# Charge_Amp.net
KiCad netlist of a schematic drawn in Altium Designer
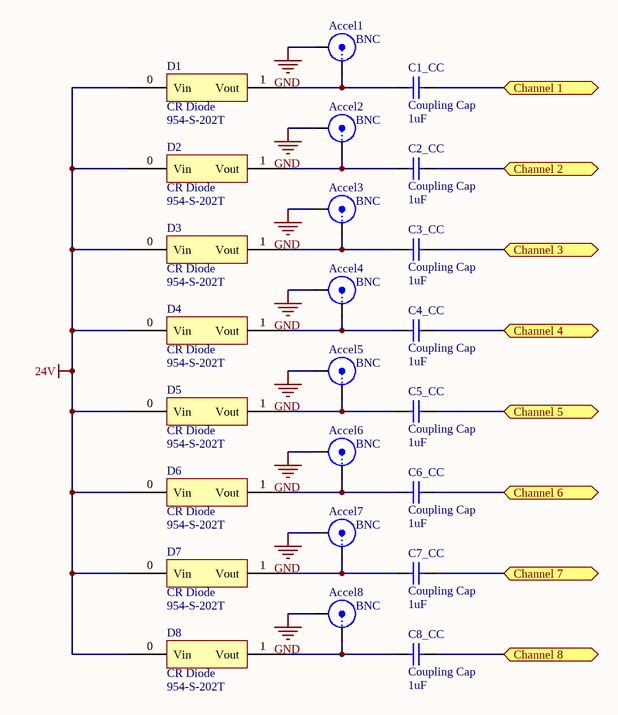
[diagram p0: Charge Amp.SchDoc]

(export (version "E")
  (design (tool "Eeschema 10.0.6"))
  (components
    (comp (ref "Accel1")
      (value "BNC")
      (footprint "BNC_RA CON")
      (description "BNC Elbow Connector")
      (fields (field (name "PUBLISHER") "Altium Limited"))
      (libsource (lib "Miscellaneous Connectors") (part "BNC"))
    )
    (comp (ref "Accel2")
      (value "BNC")
      (footprint "BNC_RA CON")
      (description "BNC Elbow Connector")
      (fields (field (name "PUBLISHER") "Altium Limited"))
      (libsource (lib "Miscellaneous Connectors") (part "BNC"))
    )
    (comp (ref "Accel3")
      (value "BNC")
      (footprint "BNC_RA CON")
      (description "BNC Elbow Connector")
      (fields (field (name "PUBLISHER") "Altium Limited"))
      (libsource (lib "Miscellaneous Connectors") (part "BNC"))
    )
    (comp (ref "Accel4")
      (value "BNC")
      (footprint "BNC_RA CON")
      (description "BNC Elbow Connector")
      (fields (field (name "PUBLISHER") "Altium Limited"))
      (libsource (lib "Miscellaneous Connectors") (part "BNC"))
    )
    (comp (ref "Accel5")
      (value "BNC")
      (footprint "BNC_RA CON")
      (description "BNC Elbow Connector")
      (fields (field (name "PUBLISHER") "Altium Limited"))
      (libsource (lib "Miscellaneous Connectors") (part "BNC"))
    )
    (comp (ref "Accel6")
      (value "BNC")
      (footprint "BNC_RA CON")
      (description "BNC Elbow Connector")
      (fields (field (name "PUBLISHER") "Altium Limited"))
      (libsource (lib "Miscellaneous Connectors") (part "BNC"))
    )
    (comp (ref "Accel7")
      (value "BNC")
      (footprint "BNC_RA CON")
      (description "BNC Elbow Connector")
      (fields (field (name "PUBLISHER") "Altium Limited"))
      (libsource (lib "Miscellaneous Connectors") (part "BNC"))
    )
    (comp (ref "Accel8")
      (value "BNC")
      (footprint "BNC_RA CON")
      (description "BNC Elbow Connector")
      (fields (field (name "PUBLISHER") "Altium Limited"))
      (libsource (lib "Miscellaneous Connectors") (part "BNC"))
    )
    (comp (ref "C1_CC")
      (value "Coupling Cap")
      (footprint "C1206")
      (description "Capacitor (Semiconductor SIM Model)")
      (fields (field (name "ALTIUM_VALUE") "1uF") (field (name "PUBLISHER") "Altium Limited"))
      (libsource (lib "Miscellaneous Devices") (part "Cap Semi"))
    )
    (comp (ref "C2_CC")
      (value "Coupling Cap")
      (footprint "C1206")
      (description "Capacitor (Semiconductor SIM Model)")
      (fields (field (name "ALTIUM_VALUE") "1uF") (field (name "PUBLISHER") "Altium Limited"))
      (libsource (lib "Miscellaneous Devices") (part "Cap Semi"))
    )
    (comp (ref "C3_CC")
      (value "Coupling Cap")
      (footprint "C1206")
      (description "Capacitor (Semiconductor SIM Model)")
      (fields (field (name "ALTIUM_VALUE") "1uF") (field (name "PUBLISHER") "Altium Limited"))
      (libsource (lib "Miscellaneous Devices") (part "Cap Semi"))
    )
    (comp (ref "C4_CC")
      (value "Coupling Cap")
      (footprint "C1206")
      (description "Capacitor (Semiconductor SIM Model)")
      (fields (field (name "ALTIUM_VALUE") "1uF") (field (name "PUBLISHER") "Altium Limited"))
      (libsource (lib "Miscellaneous Devices") (part "Cap Semi"))
    )
    (comp (ref "C5_CC")
      (value "Coupling Cap")
      (footprint "C1206")
      (description "Capacitor (Semiconductor SIM Model)")
      (fields (field (name "ALTIUM_VALUE") "1uF") (field (name "PUBLISHER") "Altium Limited"))
      (libsource (lib "Miscellaneous Devices") (part "Cap Semi"))
    )
    (comp (ref "C6_CC")
      (value "Coupling Cap")
      (footprint "C1206")
      (description "Capacitor (Semiconductor SIM Model)")
      (fields (field (name "ALTIUM_VALUE") "1uF") (field (name "PUBLISHER") "Altium Limited"))
      (libsource (lib "Miscellaneous Devices") (part "Cap Semi"))
    )
    (comp (ref "C7_CC")
      (value "Coupling Cap")
      (footprint "C1206")
      (description "Capacitor (Semiconductor SIM Model)")
      (fields (field (name "ALTIUM_VALUE") "1uF") (field (name "PUBLISHER") "Altium Limited"))
      (libsource (lib "Miscellaneous Devices") (part "Cap Semi"))
    )
    (comp (ref "C8_CC")
      (value "Coupling Cap")
      (footprint "C1206")
      (description "Capacitor (Semiconductor SIM Model)")
      (fields (field (name "ALTIUM_VALUE") "1uF") (field (name "PUBLISHER") "Altium Limited"))
      (libsource (lib "Miscellaneous Devices") (part "Cap Semi"))
    )
    (comp (ref "D1")
      (value "CR Diode")
      (footprint "CR Diode - duplicate1")
      (description "Current Regulator Diodes 100V 2mA")
      (fields (field (name "SUPPLIER PART NUMBER 1") "954-S-202T"))
      (libsource (lib "S-202T") (part "Diode_1"))
    )
    (comp (ref "D2")
      (value "CR Diode")
      (footprint "CR Diode - duplicate1")
      (description "Current Regulator Diodes 100V 2mA")
      (fields (field (name "SUPPLIER PART NUMBER 1") "954-S-202T"))
      (libsource (lib "S-202T") (part "Diode_1"))
    )
    (comp (ref "D3")
      (value "CR Diode")
      (footprint "CR Diode - duplicate1")
      (description "Current Regulator Diodes 100V 2mA")
      (fields (field (name "SUPPLIER PART NUMBER 1") "954-S-202T"))
      (libsource (lib "S-202T") (part "Diode_1"))
    )
    (comp (ref "D4")
      (value "CR Diode")
      (footprint "CR Diode - duplicate1")
      (description "Current Regulator Diodes 100V 2mA")
      (fields (field (name "SUPPLIER PART NUMBER 1") "954-S-202T"))
      (libsource (lib "S-202T") (part "Diode_1"))
    )
    (comp (ref "D5")
      (value "CR Diode")
      (footprint "CR Diode - duplicate1")
      (description "Current Regulator Diodes 100V 2mA")
      (fields (field (name "SUPPLIER PART NUMBER 1") "954-S-202T"))
      (libsource (lib "S-202T") (part "Diode_1"))
    )
    (comp (ref "D6")
      (value "CR Diode")
      (footprint "CR Diode - duplicate1")
      (description "Current Regulator Diodes 100V 2mA")
      (fields (field (name "SUPPLIER PART NUMBER 1") "954-S-202T"))
      (libsource (lib "S-202T") (part "Diode_1"))
    )
    (comp (ref "D7")
      (value "CR Diode")
      (footprint "CR Diode - duplicate1")
      (description "Current Regulator Diodes 100V 2mA")
      (fields (field (name "SUPPLIER PART NUMBER 1") "954-S-202T"))
      (libsource (lib "S-202T") (part "Diode_1"))
    )
    (comp (ref "D8")
      (value "CR Diode")
      (footprint "CR Diode - duplicate1")
      (description "Current Regulator Diodes 100V 2mA")
      (fields (field (name "SUPPLIER PART NUMBER 1") "954-S-202T"))
      (libsource (lib "S-202T") (part "Diode_1"))
    )
  )
  (nets
    (net (code "1") (name "/Channel 1") (class "Default")
      (node (ref "C1_CC") (pin "2") (pinfunction "2_2") (pintype "passive"))
    )
    (net (code "2") (name "/Channel 2") (class "Default")
      (node (ref "C2_CC") (pin "2") (pinfunction "2_2") (pintype "passive"))
    )
    (net (code "3") (name "/Channel 3") (class "Default")
      (node (ref "C3_CC") (pin "2") (pinfunction "2_2") (pintype "passive"))
    )
    (net (code "4") (name "/Channel 4") (class "Default")
      (node (ref "C4_CC") (pin "2") (pinfunction "2_2") (pintype "passive"))
    )
    (net (code "5") (name "/Channel 5") (class "Default")
      (node (ref "C5_CC") (pin "2") (pinfunction "2_2") (pintype "passive"))
    )
    (net (code "6") (name "/Channel 6") (class "Default")
      (node (ref "C6_CC") (pin "2") (pinfunction "2_2") (pintype "passive"))
    )
    (net (code "7") (name "/Channel 7") (class "Default")
      (node (ref "C7_CC") (pin "2") (pinfunction "2_2") (pintype "passive"))
    )
    (net (code "8") (name "/Channel 8") (class "Default")
      (node (ref "C8_CC") (pin "2") (pinfunction "2_2") (pintype "passive"))
    )
    (net (code "9") (name "24V") (class "Default")
      (node (ref "D1") (pin "0") (pinfunction "Vin_0") (pintype "passive"))
      (node (ref "D2") (pin "0") (pinfunction "Vin_0") (pintype "passive"))
      (node (ref "D3") (pin "0") (pinfunction "Vin_0") (pintype "passive"))
      (node (ref "D4") (pin "0") (pinfunction "Vin_0") (pintype "passive"))
      (node (ref "D5") (pin "0") (pinfunction "Vin_0") (pintype "passive"))
      (node (ref "D6") (pin "0") (pinfunction "Vin_0") (pintype "passive"))
      (node (ref "D7") (pin "0") (pinfunction "Vin_0") (pintype "passive"))
      (node (ref "D8") (pin "0") (pinfunction "Vin_0") (pintype "passive"))
    )
    (net (code "10") (name "GND") (class "Default")
      (node (ref "Accel1") (pin "2") (pinfunction "Y_2") (pintype "passive"))
      (node (ref "Accel2") (pin "2") (pinfunction "Y_2") (pintype "passive"))
      (node (ref "Accel3") (pin "2") (pinfunction "Y_2") (pintype "passive"))
      (node (ref "Accel4") (pin "2") (pinfunction "Y_2") (pintype "passive"))
      (node (ref "Accel5") (pin "2") (pinfunction "Y_2") (pintype "passive"))
      (node (ref "Accel6") (pin "2") (pinfunction "Y_2") (pintype "passive"))
      (node (ref "Accel7") (pin "2") (pinfunction "Y_2") (pintype "passive"))
      (node (ref "Accel8") (pin "2") (pinfunction "Y_2") (pintype "passive"))
    )
    (net (code "11") (name "Net-(Accel1-X)") (class "Default")
      (node (ref "Accel1") (pin "1") (pinfunction "X_1") (pintype "passive"))
      (node (ref "C1_CC") (pin "1") (pinfunction "1_1") (pintype "passive"))
      (node (ref "D1") (pin "1") (pinfunction "Vout_1") (pintype "passive"))
    )
    (net (code "12") (name "Net-(Accel2-X)") (class "Default")
      (node (ref "Accel2") (pin "1") (pinfunction "X_1") (pintype "passive"))
      (node (ref "C2_CC") (pin "1") (pinfunction "1_1") (pintype "passive"))
      (node (ref "D2") (pin "1") (pinfunction "Vout_1") (pintype "passive"))
    )
    (net (code "13") (name "Net-(Accel3-X)") (class "Default")
      (node (ref "Accel3") (pin "1") (pinfunction "X_1") (pintype "passive"))
      (node (ref "C3_CC") (pin "1") (pinfunction "1_1") (pintype "passive"))
      (node (ref "D3") (pin "1") (pinfunction "Vout_1") (pintype "passive"))
    )
    (net (code "14") (name "Net-(Accel4-X)") (class "Default")
      (node (ref "Accel4") (pin "1") (pinfunction "X_1") (pintype "passive"))
      (node (ref "C4_CC") (pin "1") (pinfunction "1_1") (pintype "passive"))
      (node (ref "D4") (pin "1") (pinfunction "Vout_1") (pintype "passive"))
    )
    (net (code "15") (name "Net-(Accel5-X)") (class "Default")
      (node (ref "Accel5") (pin "1") (pinfunction "X_1") (pintype "passive"))
      (node (ref "C5_CC") (pin "1") (pinfunction "1_1") (pintype "passive"))
      (node (ref "D5") (pin "1") (pinfunction "Vout_1") (pintype "passive"))
    )
    (net (code "16") (name "Net-(Accel6-X)") (class "Default")
      (node (ref "Accel6") (pin "1") (pinfunction "X_1") (pintype "passive"))
      (node (ref "C6_CC") (pin "1") (pinfunction "1_1") (pintype "passive"))
      (node (ref "D6") (pin "1") (pinfunction "Vout_1") (pintype "passive"))
    )
    (net (code "17") (name "Net-(Accel7-X)") (class "Default")
      (node (ref "Accel7") (pin "1") (pinfunction "X_1") (pintype "passive"))
      (node (ref "C7_CC") (pin "1") (pinfunction "1_1") (pintype "passive"))
      (node (ref "D7") (pin "1") (pinfunction "Vout_1") (pintype "passive"))
    )
    (net (code "18") (name "Net-(Accel8-X)") (class "Default")
      (node (ref "Accel8") (pin "1") (pinfunction "X_1") (pintype "passive"))
      (node (ref "C8_CC") (pin "1") (pinfunction "1_1") (pintype "passive"))
      (node (ref "D8") (pin "1") (pinfunction "Vout_1") (pintype "passive"))
    )
  )
)
